# Power.net
KiCad netlist of a schematic drawn in Altium Designer
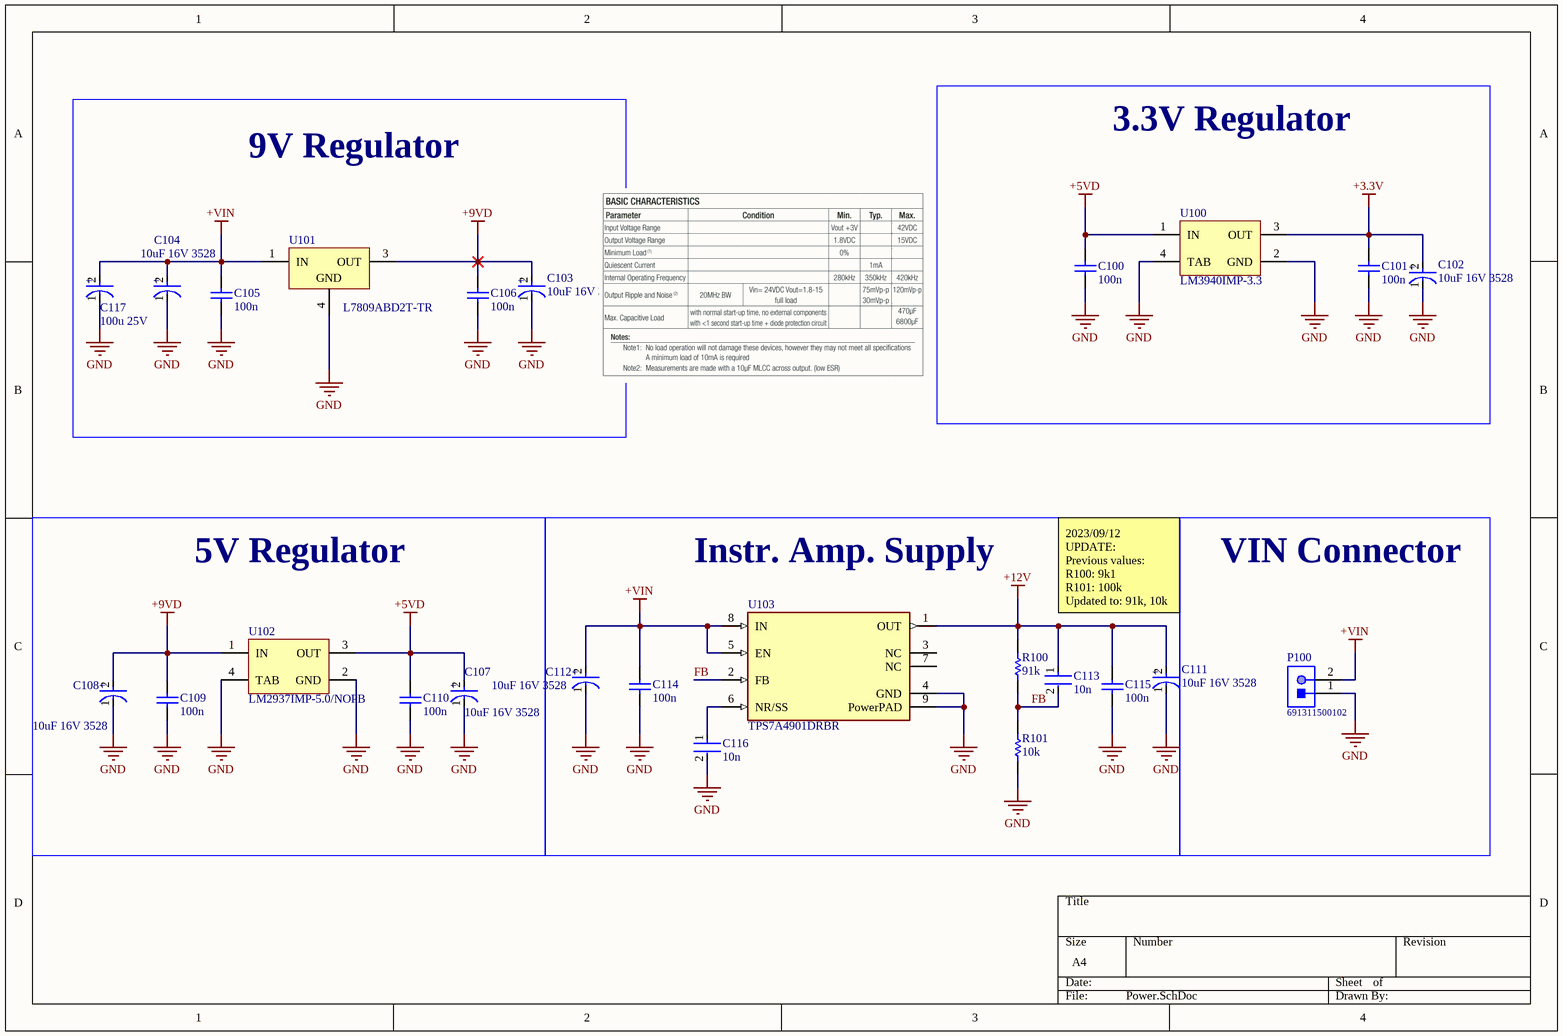
[diagram p0: Power.SchDoc]

(export (version "E")
  (design (tool "Eeschema 10.0.6"))
  (components
    (comp (ref "C100")
      (value "100n")
      (footprint "SAMS-C0603-2_M")
      (description "Multi-layer Ceramic Capacitor, -55 to 125 degC, 2-Pin SMD (0603), RoHS, Tape and Reel")
      (fields (field (name "MANUFACTURER") "Samsung Electro-Mechanics"))
      (libsource (lib "Altium Content Vault") (part "CAP-NP-2"))
    )
    (comp (ref "C101")
      (value "100n")
      (footprint "SAMS-C0603-2_M")
      (description "Multi-layer Ceramic Capacitor, -55 to 125 degC, 2-Pin SMD (0603), RoHS, Tape and Reel")
      (fields (field (name "MANUFACTURER") "Samsung Electro-Mechanics"))
      (libsource (lib "Altium Content Vault") (part "CAP-NP-2"))
    )
    (comp (ref "C102")
      (value "10uF 16V 3528")
      (footprint "FP-T491B106K020AT-MFG")
      (description "CAP TANT 10UF 10% 20V 1411")
      (fields (field (name "TOLERANCE") "10%") (field (name "VOLTAGE") "20V"))
      (libsource (lib "Altium Content Vault") (part "a00bbbee19879c290e62620ae7e47b1"))
    )
    (comp (ref "C103")
      (value "10uF 16V 3528")
      (footprint "FP-T491B106K020AT-MFG")
      (description "CAP TANT 10UF 10% 20V 1411")
      (fields (field (name "TOLERANCE") "10%") (field (name "VOLTAGE") "20V"))
      (libsource (lib "Altium Content Vault") (part "a00bbbee19879c290e62620ae7e47b1"))
    )
    (comp (ref "C104")
      (value "10uF 16V 3528")
      (footprint "FP-T491B106K020AT-MFG")
      (description "CAP TANT 10UF 10% 20V 1411")
      (fields (field (name "TOLERANCE") "10%") (field (name "VOLTAGE") "20V"))
      (libsource (lib "Altium Content Vault") (part "a00bbbee19879c290e62620ae7e47b1"))
    )
    (comp (ref "C105")
      (value "100n")
      (footprint "SAMS-C0603-2_M")
      (description "Multi-layer Ceramic Capacitor, -55 to 125 degC, 2-Pin SMD (0603), RoHS, Tape and Reel")
      (fields (field (name "MANUFACTURER") "Samsung Electro-Mechanics"))
      (libsource (lib "Altium Content Vault") (part "CAP-NP-2"))
    )
    (comp (ref "C106")
      (value "100n")
      (footprint "SAMS-C0603-2_M")
      (description "Multi-layer Ceramic Capacitor, -55 to 125 degC, 2-Pin SMD (0603), RoHS, Tape and Reel")
      (fields (field (name "MANUFACTURER") "Samsung Electro-Mechanics"))
      (libsource (lib "Altium Content Vault") (part "CAP-NP-2"))
    )
    (comp (ref "C107")
      (value "10uF 16V 3528")
      (footprint "FP-T491B106K020AT-MFG")
      (description "CAP TANT 10UF 10% 20V 1411")
      (fields (field (name "TOLERANCE") "10%") (field (name "VOLTAGE") "20V"))
      (libsource (lib "Altium Content Vault") (part "a00bbbee19879c290e62620ae7e47b1"))
    )
    (comp (ref "C108")
      (value "10uF 16V 3528")
      (footprint "FP-T491B106K020AT-MFG")
      (description "CAP TANT 10UF 10% 20V 1411")
      (fields (field (name "TOLERANCE") "10%") (field (name "VOLTAGE") "20V"))
      (libsource (lib "Altium Content Vault") (part "a00bbbee19879c290e62620ae7e47b1"))
    )
    (comp (ref "C109")
      (value "100n")
      (footprint "SAMS-C0603-2_M")
      (description "Multi-layer Ceramic Capacitor, -55 to 125 degC, 2-Pin SMD (0603), RoHS, Tape and Reel")
      (fields (field (name "MANUFACTURER") "Samsung Electro-Mechanics"))
      (libsource (lib "Altium Content Vault") (part "CAP-NP-2"))
    )
    (comp (ref "C110")
      (value "100n")
      (footprint "SAMS-C0603-2_M")
      (description "Multi-layer Ceramic Capacitor, -55 to 125 degC, 2-Pin SMD (0603), RoHS, Tape and Reel")
      (fields (field (name "MANUFACTURER") "Samsung Electro-Mechanics"))
      (libsource (lib "Altium Content Vault") (part "CAP-NP-2"))
    )
    (comp (ref "C111")
      (value "10uF 16V 3528")
      (footprint "FP-T491B106K020AT-MFG")
      (description "CAP TANT 10UF 10% 20V 1411")
      (fields (field (name "TOLERANCE") "10%") (field (name "VOLTAGE") "20V"))
      (libsource (lib "Altium Content Vault") (part "a00bbbee19879c290e62620ae7e47b1"))
    )
    (comp (ref "C112")
      (value "10uF 16V 3528")
      (footprint "FP-T491B106K020AT-MFG")
      (description "CAP TANT 10UF 10% 20V 1411")
      (fields (field (name "TOLERANCE") "10%") (field (name "VOLTAGE") "20V"))
      (libsource (lib "Altium Content Vault") (part "a00bbbee19879c290e62620ae7e47b1"))
    )
    (comp (ref "C113")
      (value "10n")
      (footprint "FP-C0603C-CF-MFG")
      (description "CAP CER 10000PF 200V X7R 0603")
      (fields
        (field (name "MANUFACTURER") "KEMET")
        (field (name "MANUFACTURER PART NUMBER") "C0603C103K2RACTU")
      )
      (libsource (lib "Altium Content Vault") (part "b4654b650e69147ec39a6b967a45e02"))
    )
    (comp (ref "C114")
      (value "100n")
      (footprint "SAMS-C0603-2_M")
      (description "Multi-layer Ceramic Capacitor, -55 to 125 degC, 2-Pin SMD (0603), RoHS, Tape and Reel")
      (fields (field (name "MANUFACTURER") "Samsung Electro-Mechanics"))
      (libsource (lib "Altium Content Vault") (part "CAP-NP-2"))
    )
    (comp (ref "C115")
      (value "100n")
      (footprint "SAMS-C0603-2_M")
      (description "Multi-layer Ceramic Capacitor, -55 to 125 degC, 2-Pin SMD (0603), RoHS, Tape and Reel")
      (fields (field (name "MANUFACTURER") "Samsung Electro-Mechanics"))
      (libsource (lib "Altium Content Vault") (part "CAP-NP-2"))
    )
    (comp (ref "C116")
      (value "10n")
      (footprint "FP-C0603C-CF-MFG")
      (description "CAP CER 10000PF 200V X7R 0603")
      (fields
        (field (name "MANUFACTURER") "KEMET")
        (field (name "MANUFACTURER PART NUMBER") "C0603C103K2RACTU")
      )
      (libsource (lib "Altium Content Vault") (part "b4654b650e69147ec39a6b967a45e02"))
    )
    (comp (ref "C117")
      (value "100u 25V")
      (footprint "FP-T491X107K025AT-MFG")
      (description "CAP TANT 100UF 10% 25V 2917")
      (fields (field (name "TOLERANCE") "10%") (field (name "VOLTAGE") "25V"))
      (libsource (lib "Altium Content Vault") (part "cf48714ba7e38822c1575c7ec0b6d1f"))
    )
    (comp (ref "P100")
      (value "691311500102")
      (footprint "691311500102")
      (description "Serie 311 - 5.08mm Close Vertical PCB Header WR-TBL, 2 pin")
      (fields (field (name "MANUFACTURER") "Wurth Elektronik") (field (name "PUBLISHER") "WurthElektronik"))
      (libsource (lib "Altium Content Vault") (part "WE-CN-1P-M-R2"))
    )
    (comp (ref "R100")
      (value "91k")
      (footprint "RESC1608X55X30ML15T15")
      (fields (field (name "MANUFACTURER") "Panasonic") (field (name "PART NUMBER") "ERJ-3EKF9100V"))
      (libsource (lib "Altium Content Vault") (part "RES"))
    )
    (comp (ref "R101")
      (value "10k")
      (footprint "RESC1608X55X30ML15T15")
      (fields (field (name "PART NUMBER") "ERJ-3EKF1003V") (field (name "MANUFACTURER") "Panasonic"))
      (libsource (lib "Altium Content Vault") (part "RES"))
    )
    (comp (ref "U100")
      (value "LM3940IMP-3.3")
      (footprint "DCY0004A_L")
      (description "1A Low Dropout Regulator for 5V to 3.3V Conversion, 4-pin SOT-223")
      (fields (field (name "MANUFACTURER") "Texas Instruments"))
      (libsource (lib "Altium Content Vault") (part "PM-REG-LM2940-TO4"))
    )
    (comp (ref "U101")
      (value "L7809ABD2T-TR")
      (footprint "TO-263_N")
      (description "Positive Voltage Regulator, 3-Pin D2PAK, Tape and Reel")
      (libsource (lib "Altium Content Vault") (part "PM-REG-L4940-SOT3"))
    )
    (comp (ref "U102")
      (value "LM2937IMP-5.0/NOPB")
      (footprint "DCY0004A_L")
      (description "500 mA Low Dropout Regulator, 4-pin SOT-223, Pb-Free")
      (fields (field (name "MANUFACTURER") "Texas Instruments"))
      (libsource (lib "Altium Content Vault") (part "PM-REG-LM2940-TO4"))
    )
    (comp (ref "U103")
      (value "TPS7A4901DRBR")
      (footprint "FP-DRB0008A-MFG")
      (description "None")
      (libsource (lib "Altium Content Vault") (part "ef16affa275921b576f8415521af00b"))
    )
  )
  (nets
    (net (code "1") (name "+3.3V") (class "Default")
      (node (ref "C101") (pin "2") (pinfunction "2_2") (pintype "passive"))
      (node (ref "C102") (pin "2") (pinfunction "A_2") (pintype "passive"))
      (node (ref "U100") (pin "3") (pinfunction "OUT_3") (pintype "power_in"))
    )
    (net (code "2") (name "+5VD") (class "Default")
      (node (ref "C100") (pin "2") (pinfunction "2_2") (pintype "passive"))
      (node (ref "C107") (pin "2") (pinfunction "A_2") (pintype "passive"))
      (node (ref "C110") (pin "2") (pinfunction "2_2") (pintype "passive"))
      (node (ref "U100") (pin "1") (pinfunction "IN_1") (pintype "power_in"))
      (node (ref "U102") (pin "3") (pinfunction "OUT_3") (pintype "power_in"))
    )
    (net (code "3") (name "+9VD") (class "Default")
      (node (ref "C103") (pin "2") (pinfunction "A_2") (pintype "passive"))
      (node (ref "C106") (pin "2") (pinfunction "2_2") (pintype "passive"))
      (node (ref "C108") (pin "2") (pinfunction "A_2") (pintype "passive"))
      (node (ref "C109") (pin "2") (pinfunction "2_2") (pintype "passive"))
      (node (ref "U101") (pin "3") (pinfunction "OUT_3") (pintype "power_in"))
      (node (ref "U102") (pin "1") (pinfunction "IN_1") (pintype "power_in"))
    )
    (net (code "4") (name "+12V") (class "Default")
      (node (ref "C111") (pin "2") (pinfunction "A_2") (pintype "passive"))
      (node (ref "C113") (pin "1") (pinfunction "1_1") (pintype "passive"))
      (node (ref "C115") (pin "2") (pinfunction "2_2") (pintype "passive"))
      (node (ref "R100") (pin "2") (pinfunction "2_2") (pintype "passive"))
      (node (ref "U103") (pin "1") (pinfunction "OUT_1") (pintype "output"))
    )
    (net (code "5") (name "+VIN") (class "Default")
      (node (ref "C104") (pin "2") (pinfunction "A_2") (pintype "passive"))
      (node (ref "C105") (pin "2") (pinfunction "2_2") (pintype "passive"))
      (node (ref "C112") (pin "2") (pinfunction "A_2") (pintype "passive"))
      (node (ref "C114") (pin "2") (pinfunction "2_2") (pintype "passive"))
      (node (ref "C117") (pin "2") (pinfunction "A_2") (pintype "passive"))
      (node (ref "P100") (pin "2") (pinfunction "2_2") (pintype "passive"))
      (node (ref "U101") (pin "1") (pinfunction "IN_1") (pintype "power_in"))
      (node (ref "U103") (pin "5") (pinfunction "EN_5") (pintype "input"))
      (node (ref "U103") (pin "8") (pinfunction "IN_8") (pintype "input"))
    )
    (net (code "6") (name "/FB") (class "Default")
      (node (ref "C113") (pin "2") (pinfunction "2_2") (pintype "passive"))
      (node (ref "R100") (pin "1") (pinfunction "1_1") (pintype "passive"))
      (node (ref "R101") (pin "2") (pinfunction "2_2") (pintype "passive"))
      (node (ref "U103") (pin "2") (pinfunction "FB_2") (pintype "input"))
    )
    (net (code "7") (name "GND") (class "Default")
      (node (ref "C100") (pin "1") (pinfunction "1_1") (pintype "passive"))
      (node (ref "C101") (pin "1") (pinfunction "1_1") (pintype "passive"))
      (node (ref "C102") (pin "1") (pinfunction "C_1") (pintype "passive"))
      (node (ref "C103") (pin "1") (pinfunction "C_1") (pintype "passive"))
      (node (ref "C104") (pin "1") (pinfunction "C_1") (pintype "passive"))
      (node (ref "C105") (pin "1") (pinfunction "1_1") (pintype "passive"))
      (node (ref "C106") (pin "1") (pinfunction "1_1") (pintype "passive"))
      (node (ref "C107") (pin "1") (pinfunction "C_1") (pintype "passive"))
      (node (ref "C108") (pin "1") (pinfunction "C_1") (pintype "passive"))
      (node (ref "C109") (pin "1") (pinfunction "1_1") (pintype "passive"))
      (node (ref "C110") (pin "1") (pinfunction "1_1") (pintype "passive"))
      (node (ref "C111") (pin "1") (pinfunction "C_1") (pintype "passive"))
      (node (ref "C112") (pin "1") (pinfunction "C_1") (pintype "passive"))
      (node (ref "C114") (pin "1") (pinfunction "1_1") (pintype "passive"))
      (node (ref "C115") (pin "1") (pinfunction "1_1") (pintype "passive"))
      (node (ref "C116") (pin "2") (pinfunction "2_2") (pintype "passive"))
      (node (ref "C117") (pin "1") (pinfunction "C_1") (pintype "passive"))
      (node (ref "P100") (pin "1") (pinfunction "1_1") (pintype "passive"))
      (node (ref "R101") (pin "1") (pinfunction "1_1") (pintype "passive"))
      (node (ref "U100") (pin "2") (pinfunction "GND_2") (pintype "power_in"))
      (node (ref "U100") (pin "4") (pinfunction "TAB_4") (pintype "power_in"))
      (node (ref "U101") (pin "4") (pinfunction "GND_4") (pintype "power_in"))
      (node (ref "U102") (pin "2") (pinfunction "GND_2") (pintype "power_in"))
      (node (ref "U102") (pin "4") (pinfunction "TAB_4") (pintype "power_in"))
      (node (ref "U103") (pin "4") (pinfunction "GND_4") (pintype "power_in"))
      (node (ref "U103") (pin "9") (pinfunction "PowerPAD_9") (pintype "power_in"))
    )
    (net (code "8") (name "Net-(U103-NR{slash}SS)") (class "Default")
      (node (ref "C116") (pin "1") (pinfunction "1_1") (pintype "passive"))
      (node (ref "U103") (pin "6") (pinfunction "NR/SS_6") (pintype "input"))
    )
    (net (code "9") (name "unconnected-(U103-NC-Pad3)") (class "Default")
      (node (ref "U103") (pin "3") (pinfunction "NC_3") (pintype "passive"))
    )
    (net (code "10") (name "unconnected-(U103-NC-Pad7)") (class "Default")
      (node (ref "U103") (pin "7") (pinfunction "NC_7") (pintype "passive"))
    )
  )
)
